# satshakit_cnc_20mhz.net
KiCad netlist of a schematic drawn in EAGLE
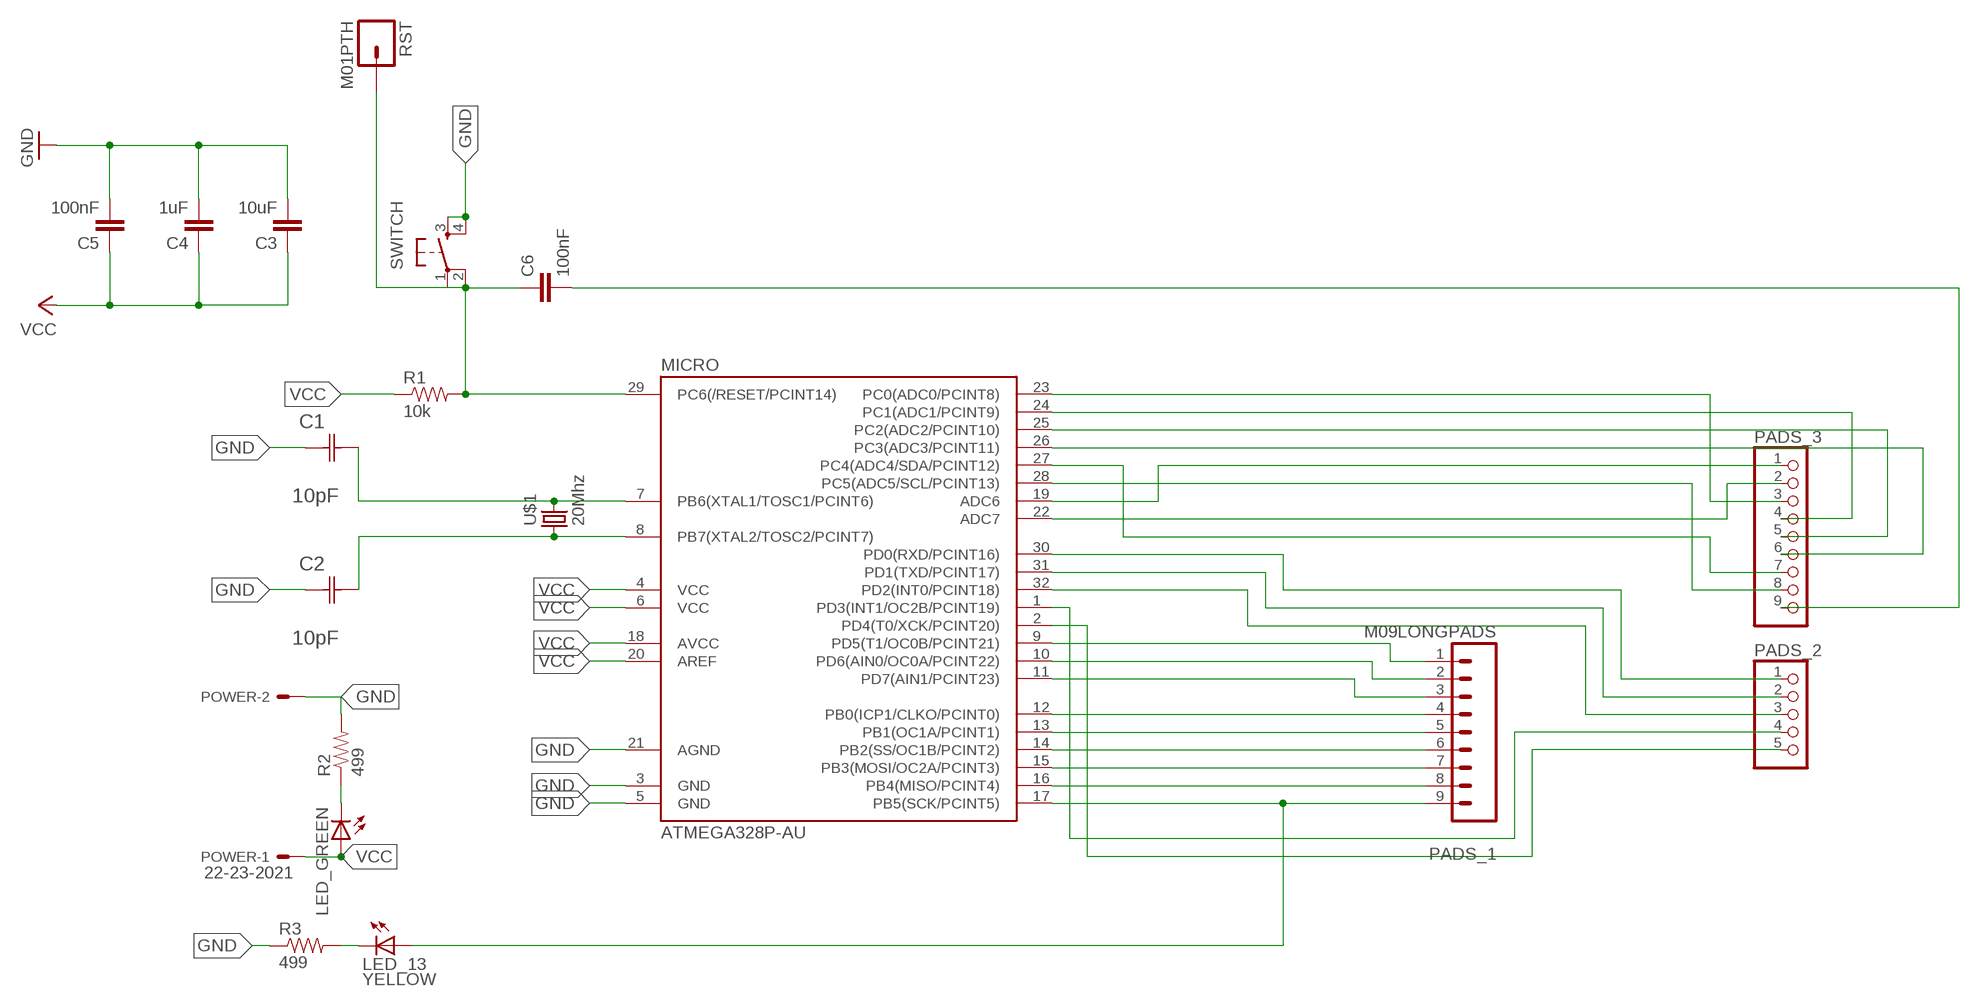
[diagram p0: schematic, sheet 1]

(export (version "E")
  (design (tool "Eeschema 10.0.6"))
  (components
    (comp (ref "C1")
      (value "10pF")
      (footprint "eagle-import:CAPC3216X178N")
      (fields (field (name "MPN") "0612ZC225MAT2A") (field (name "TOLERANCE") "±20%"))
      (libsource (lib "eagle-import") (part "0612ZC225MAT2A"))
    )
    (comp (ref "C2")
      (value "10pF")
      (footprint "eagle-import:CAPC3216X178N")
      (fields (field (name "MPN") "0612ZC225MAT2A") (field (name "TOLERANCE") "±20%"))
      (libsource (lib "eagle-import") (part "0612ZC225MAT2A"))
    )
    (comp (ref "C3")
      (value "10uF")
      (footprint "eagle-import:1206")
      (libsource (lib "eagle-import") (part "CAP1206"))
    )
    (comp (ref "C4")
      (value "1uF")
      (footprint "eagle-import:1206")
      (libsource (lib "eagle-import") (part "CAP1206"))
    )
    (comp (ref "C5")
      (value "100nF")
      (footprint "eagle-import:1206")
      (libsource (lib "eagle-import") (part "CAP1206"))
    )
    (comp (ref "C6")
      (value "100nF")
      (footprint "eagle-import:1206")
      (libsource (lib "eagle-import") (part "CAP1206"))
    )
    (comp (ref "LED_13")
      (value "YELLOW")
      (footprint "eagle-import:1206")
      (libsource (lib "eagle-import") (part "LED1206"))
    )
    (comp (ref "LED_GREEN")
      (value "LED1206")
      (footprint "eagle-import:1206")
      (libsource (lib "eagle-import") (part "LED1206"))
    )
    (comp (ref "MICRO")
      (value "ATMEGA328P-AU")
      (footprint "eagle-import:TQFP32-08")
      (libsource (lib "eagle-import") (part "ATMEGA48/88/168-AU"))
    )
    (comp (ref "PADS_1")
      (value "M09LONGPADS")
      (footprint "eagle-import:1X09_LONGPADS")
      (libsource (lib "eagle-import") (part "M09LONGPADS"))
    )
    (comp (ref "PADS_2")
      (value "PINHD-1X5")
      (footprint "eagle-import:1X05")
      (libsource (lib "eagle-import") (part "PINHD-1X5"))
    )
    (comp (ref "PADS_3")
      (value "PINHD-1X9")
      (footprint "eagle-import:1X09")
      (libsource (lib "eagle-import") (part "PINHD-1X9"))
    )
    (comp (ref "POWER")
      (value "22-23-2021")
      (footprint "eagle-import:22-23-2021")
      (fields (field (name "MF") "MOLEX"))
      (libsource (lib "eagle-import") (part "22-23-2021"))
    )
    (comp (ref "R1")
      (value "10k")
      (footprint "eagle-import:1206")
      (libsource (lib "eagle-import") (part "RESISTOR1206"))
    )
    (comp (ref "R2")
      (value "499")
      (footprint "eagle-import:1206")
      (libsource (lib "eagle-import") (part "RESISTOR1206"))
    )
    (comp (ref "R3")
      (value "499")
      (footprint "eagle-import:1206")
      (libsource (lib "eagle-import") (part "RESISTOR1206"))
    )
    (comp (ref "RST")
      (value "M01PTH")
      (footprint "eagle-import:1X01")
      (libsource (lib "eagle-import") (part "M01PTH"))
    )
    (comp (ref "SWITCH")
      (value "6MM_SWITCH6MM_SWITCH")
      (footprint "eagle-import:6MM_SWITCH")
      (libsource (lib "eagle-import") (part "6MM_SWITCH6MM_SWITCH"))
    )
    (comp (ref "U$1")
      (value "20Mhz")
      (footprint "eagle-import:2-SMD-5X3MM")
      (libsource (lib "eagle-import") (part "CRYSTAL"))
    )
  )
  (nets
    (net (code "1") (name "GND") (class "Default")
      (node (ref "C1") (pin "1") (pinfunction "C1_1") (pintype "passive"))
      (node (ref "C2") (pin "1") (pinfunction "C1_1") (pintype "passive"))
      (node (ref "C3") (pin "2") (pinfunction "2_2") (pintype "passive"))
      (node (ref "C4") (pin "2") (pinfunction "2_2") (pintype "passive"))
      (node (ref "C5") (pin "2") (pinfunction "2_2") (pintype "passive"))
      (node (ref "MICRO") (pin "21") (pinfunction "AGND_21") (pintype "power_in"))
      (node (ref "MICRO") (pin "3") (pinfunction "GND_3") (pintype "power_in"))
      (node (ref "MICRO") (pin "5") (pinfunction "GND_5") (pintype "power_in"))
      (node (ref "POWER") (pin "2") (pinfunction "S_2") (pintype "passive"))
      (node (ref "R2") (pin "2") (pinfunction "2_2") (pintype "passive"))
      (node (ref "R3") (pin "1") (pinfunction "1_1") (pintype "passive"))
      (node (ref "SWITCH") (pin "3") (pinfunction "S_3") (pintype "passive"))
      (node (ref "SWITCH") (pin "4") (pinfunction "S1_4") (pintype "passive"))
    )
    (net (code "2") (name "Net-(C1-C2)") (class "Default")
      (node (ref "C1") (pin "2") (pinfunction "C2_2") (pintype "passive"))
      (node (ref "MICRO") (pin "7") (pinfunction "PB6(XTAL1/TOSC1/PCINT6)_7") (pintype "bidirectional"))
      (node (ref "U$1") (pin "P$2") (pinfunction "2_P$2") (pintype "passive"))
    )
    (net (code "3") (name "Net-(C2-C2)") (class "Default")
      (node (ref "C2") (pin "2") (pinfunction "C2_2") (pintype "passive"))
      (node (ref "MICRO") (pin "8") (pinfunction "PB7(XTAL2/TOSC2/PCINT7)_8") (pintype "bidirectional"))
      (node (ref "U$1") (pin "P$1") (pinfunction "1_P$1") (pintype "passive"))
    )
    (net (code "4") (name "Net-(C6-Pad2)") (class "Default")
      (node (ref "C6") (pin "2") (pinfunction "2_2") (pintype "passive"))
      (node (ref "PADS_3") (pin "9") (pinfunction "9_9") (pintype "passive"))
    )
    (net (code "5") (name "Net-(LED_13-A)") (class "Default")
      (node (ref "LED_13") (pin "1") (pinfunction "A_1") (pintype "passive"))
      (node (ref "MICRO") (pin "17") (pinfunction "PB5(SCK/PCINT5)_17") (pintype "bidirectional"))
      (node (ref "PADS_1") (pin "9") (pinfunction "9_9") (pintype "passive"))
    )
    (net (code "6") (name "Net-(LED_13-C)") (class "Default")
      (node (ref "LED_13") (pin "2") (pinfunction "C_2") (pintype "passive"))
      (node (ref "R3") (pin "2") (pinfunction "2_2") (pintype "passive"))
    )
    (net (code "7") (name "Net-(LED_GREEN-C)") (class "Default")
      (node (ref "LED_GREEN") (pin "2") (pinfunction "C_2") (pintype "passive"))
      (node (ref "R2") (pin "1") (pinfunction "1_1") (pintype "passive"))
    )
    (net (code "8") (name "Net-(MICRO-ADC6)") (class "Default")
      (node (ref "MICRO") (pin "19") (pinfunction "ADC6_19") (pintype "passive"))
      (node (ref "PADS_3") (pin "1") (pinfunction "1_1") (pintype "passive"))
    )
    (net (code "9") (name "Net-(MICRO-ADC7)") (class "Default")
      (node (ref "MICRO") (pin "22") (pinfunction "ADC7_22") (pintype "passive"))
      (node (ref "PADS_3") (pin "2") (pinfunction "2_2") (pintype "passive"))
    )
    (net (code "10") (name "Net-(MICRO-PB0(ICP1{slash}CLKO{slash}PCINT0))") (class "Default")
      (node (ref "MICRO") (pin "12") (pinfunction "PB0(ICP1/CLKO/PCINT0)_12") (pintype "bidirectional"))
      (node (ref "PADS_1") (pin "4") (pinfunction "4_4") (pintype "passive"))
    )
    (net (code "11") (name "Net-(MICRO-PB1(OC1A{slash}PCINT1))") (class "Default")
      (node (ref "MICRO") (pin "13") (pinfunction "PB1(OC1A/PCINT1)_13") (pintype "bidirectional"))
      (node (ref "PADS_1") (pin "5") (pinfunction "5_5") (pintype "passive"))
    )
    (net (code "12") (name "Net-(MICRO-PB2(SS{slash}OC1B{slash}PCINT2))") (class "Default")
      (node (ref "MICRO") (pin "14") (pinfunction "PB2(SS/OC1B/PCINT2)_14") (pintype "bidirectional"))
      (node (ref "PADS_1") (pin "6") (pinfunction "6_6") (pintype "passive"))
    )
    (net (code "13") (name "Net-(MICRO-PB3(MOSI{slash}OC2A{slash}PCINT3))") (class "Default")
      (node (ref "MICRO") (pin "15") (pinfunction "PB3(MOSI/OC2A/PCINT3)_15") (pintype "bidirectional"))
      (node (ref "PADS_1") (pin "7") (pinfunction "7_7") (pintype "passive"))
    )
    (net (code "14") (name "Net-(MICRO-PB4(MISO{slash}PCINT4))") (class "Default")
      (node (ref "MICRO") (pin "16") (pinfunction "PB4(MISO/PCINT4)_16") (pintype "bidirectional"))
      (node (ref "PADS_1") (pin "8") (pinfunction "8_8") (pintype "passive"))
    )
    (net (code "15") (name "Net-(MICRO-PC0(ADC0{slash}PCINT8))") (class "Default")
      (node (ref "MICRO") (pin "23") (pinfunction "PC0(ADC0/PCINT8)_23") (pintype "bidirectional"))
      (node (ref "PADS_3") (pin "3") (pinfunction "3_3") (pintype "passive"))
    )
    (net (code "16") (name "Net-(MICRO-PC1(ADC1{slash}PCINT9))") (class "Default")
      (node (ref "MICRO") (pin "24") (pinfunction "PC1(ADC1/PCINT9)_24") (pintype "bidirectional"))
      (node (ref "PADS_3") (pin "4") (pinfunction "4_4") (pintype "passive"))
    )
    (net (code "17") (name "Net-(MICRO-PC2(ADC2{slash}PCINT10))") (class "Default")
      (node (ref "MICRO") (pin "25") (pinfunction "PC2(ADC2/PCINT10)_25") (pintype "bidirectional"))
      (node (ref "PADS_3") (pin "5") (pinfunction "5_5") (pintype "passive"))
    )
    (net (code "18") (name "Net-(MICRO-PC3(ADC3{slash}PCINT11))") (class "Default")
      (node (ref "MICRO") (pin "26") (pinfunction "PC3(ADC3/PCINT11)_26") (pintype "bidirectional"))
      (node (ref "PADS_3") (pin "6") (pinfunction "6_6") (pintype "passive"))
    )
    (net (code "19") (name "Net-(MICRO-PC4(ADC4{slash}SDA{slash}PCINT12))") (class "Default")
      (node (ref "MICRO") (pin "27") (pinfunction "PC4(ADC4/SDA/PCINT12)_27") (pintype "bidirectional"))
      (node (ref "PADS_3") (pin "7") (pinfunction "7_7") (pintype "passive"))
    )
    (net (code "20") (name "Net-(MICRO-PC5(ADC5{slash}SCL{slash}PCINT13))") (class "Default")
      (node (ref "MICRO") (pin "28") (pinfunction "PC5(ADC5/SCL/PCINT13)_28") (pintype "bidirectional"))
      (node (ref "PADS_3") (pin "8") (pinfunction "8_8") (pintype "passive"))
    )
    (net (code "21") (name "Net-(MICRO-PC6({slash}RESET{slash}PCINT14))") (class "Default")
      (node (ref "C6") (pin "1") (pinfunction "1_1") (pintype "passive"))
      (node (ref "MICRO") (pin "29") (pinfunction "PC6(/RESET/PCINT14)_29") (pintype "bidirectional"))
      (node (ref "R1") (pin "2") (pinfunction "2_2") (pintype "passive"))
      (node (ref "RST") (pin "1") (pinfunction "1_1") (pintype "passive"))
      (node (ref "SWITCH") (pin "1") (pinfunction "P_1") (pintype "passive"))
      (node (ref "SWITCH") (pin "2") (pinfunction "P1_2") (pintype "passive"))
    )
    (net (code "22") (name "Net-(MICRO-PD0(RXD{slash}PCINT16))") (class "Default")
      (node (ref "MICRO") (pin "30") (pinfunction "PD0(RXD/PCINT16)_30") (pintype "bidirectional"))
      (node (ref "PADS_2") (pin "1") (pinfunction "1_1") (pintype "passive"))
    )
    (net (code "23") (name "Net-(MICRO-PD1(TXD{slash}PCINT17))") (class "Default")
      (node (ref "MICRO") (pin "31") (pinfunction "PD1(TXD/PCINT17)_31") (pintype "bidirectional"))
      (node (ref "PADS_2") (pin "2") (pinfunction "2_2") (pintype "passive"))
    )
    (net (code "24") (name "Net-(MICRO-PD2(INT0{slash}PCINT18))") (class "Default")
      (node (ref "MICRO") (pin "32") (pinfunction "PD2(INT0/PCINT18)_32") (pintype "bidirectional"))
      (node (ref "PADS_2") (pin "3") (pinfunction "3_3") (pintype "passive"))
    )
    (net (code "25") (name "Net-(MICRO-PD3(INT1{slash}OC2B{slash}PCINT19))") (class "Default")
      (node (ref "MICRO") (pin "1") (pinfunction "PD3(INT1/OC2B/PCINT19)_1") (pintype "bidirectional"))
      (node (ref "PADS_2") (pin "4") (pinfunction "4_4") (pintype "passive"))
    )
    (net (code "26") (name "Net-(MICRO-PD4(T0{slash}XCK{slash}PCINT20))") (class "Default")
      (node (ref "MICRO") (pin "2") (pinfunction "PD4(T0/XCK/PCINT20)_2") (pintype "bidirectional"))
      (node (ref "PADS_2") (pin "5") (pinfunction "5_5") (pintype "passive"))
    )
    (net (code "27") (name "Net-(MICRO-PD5(T1{slash}OC0B{slash}PCINT21))") (class "Default")
      (node (ref "MICRO") (pin "9") (pinfunction "PD5(T1/OC0B/PCINT21)_9") (pintype "bidirectional"))
      (node (ref "PADS_1") (pin "1") (pinfunction "1_1") (pintype "passive"))
    )
    (net (code "28") (name "Net-(MICRO-PD6(AIN0{slash}OC0A{slash}PCINT22))") (class "Default")
      (node (ref "MICRO") (pin "10") (pinfunction "PD6(AIN0/OC0A/PCINT22)_10") (pintype "bidirectional"))
      (node (ref "PADS_1") (pin "2") (pinfunction "2_2") (pintype "passive"))
    )
    (net (code "29") (name "Net-(MICRO-PD7(AIN1{slash}PCINT23))") (class "Default")
      (node (ref "MICRO") (pin "11") (pinfunction "PD7(AIN1/PCINT23)_11") (pintype "bidirectional"))
      (node (ref "PADS_1") (pin "3") (pinfunction "3_3") (pintype "passive"))
    )
    (net (code "30") (name "VCC") (class "Default")
      (node (ref "C3") (pin "1") (pinfunction "1_1") (pintype "passive"))
      (node (ref "C4") (pin "1") (pinfunction "1_1") (pintype "passive"))
      (node (ref "C5") (pin "1") (pinfunction "1_1") (pintype "passive"))
      (node (ref "LED_GREEN") (pin "1") (pinfunction "A_1") (pintype "passive"))
      (node (ref "MICRO") (pin "18") (pinfunction "AVCC_18") (pintype "passive"))
      (node (ref "MICRO") (pin "20") (pinfunction "AREF_20") (pintype "passive"))
      (node (ref "MICRO") (pin "4") (pinfunction "VCC_4") (pintype "power_in"))
      (node (ref "MICRO") (pin "6") (pinfunction "VCC_6") (pintype "power_in"))
      (node (ref "POWER") (pin "1") (pinfunction "S_1") (pintype "passive"))
      (node (ref "R1") (pin "1") (pinfunction "1_1") (pintype "passive"))
    )
  )
)
